# Artemis_Thing_Plus.net
KiCad netlist of a schematic drawn in EAGLE
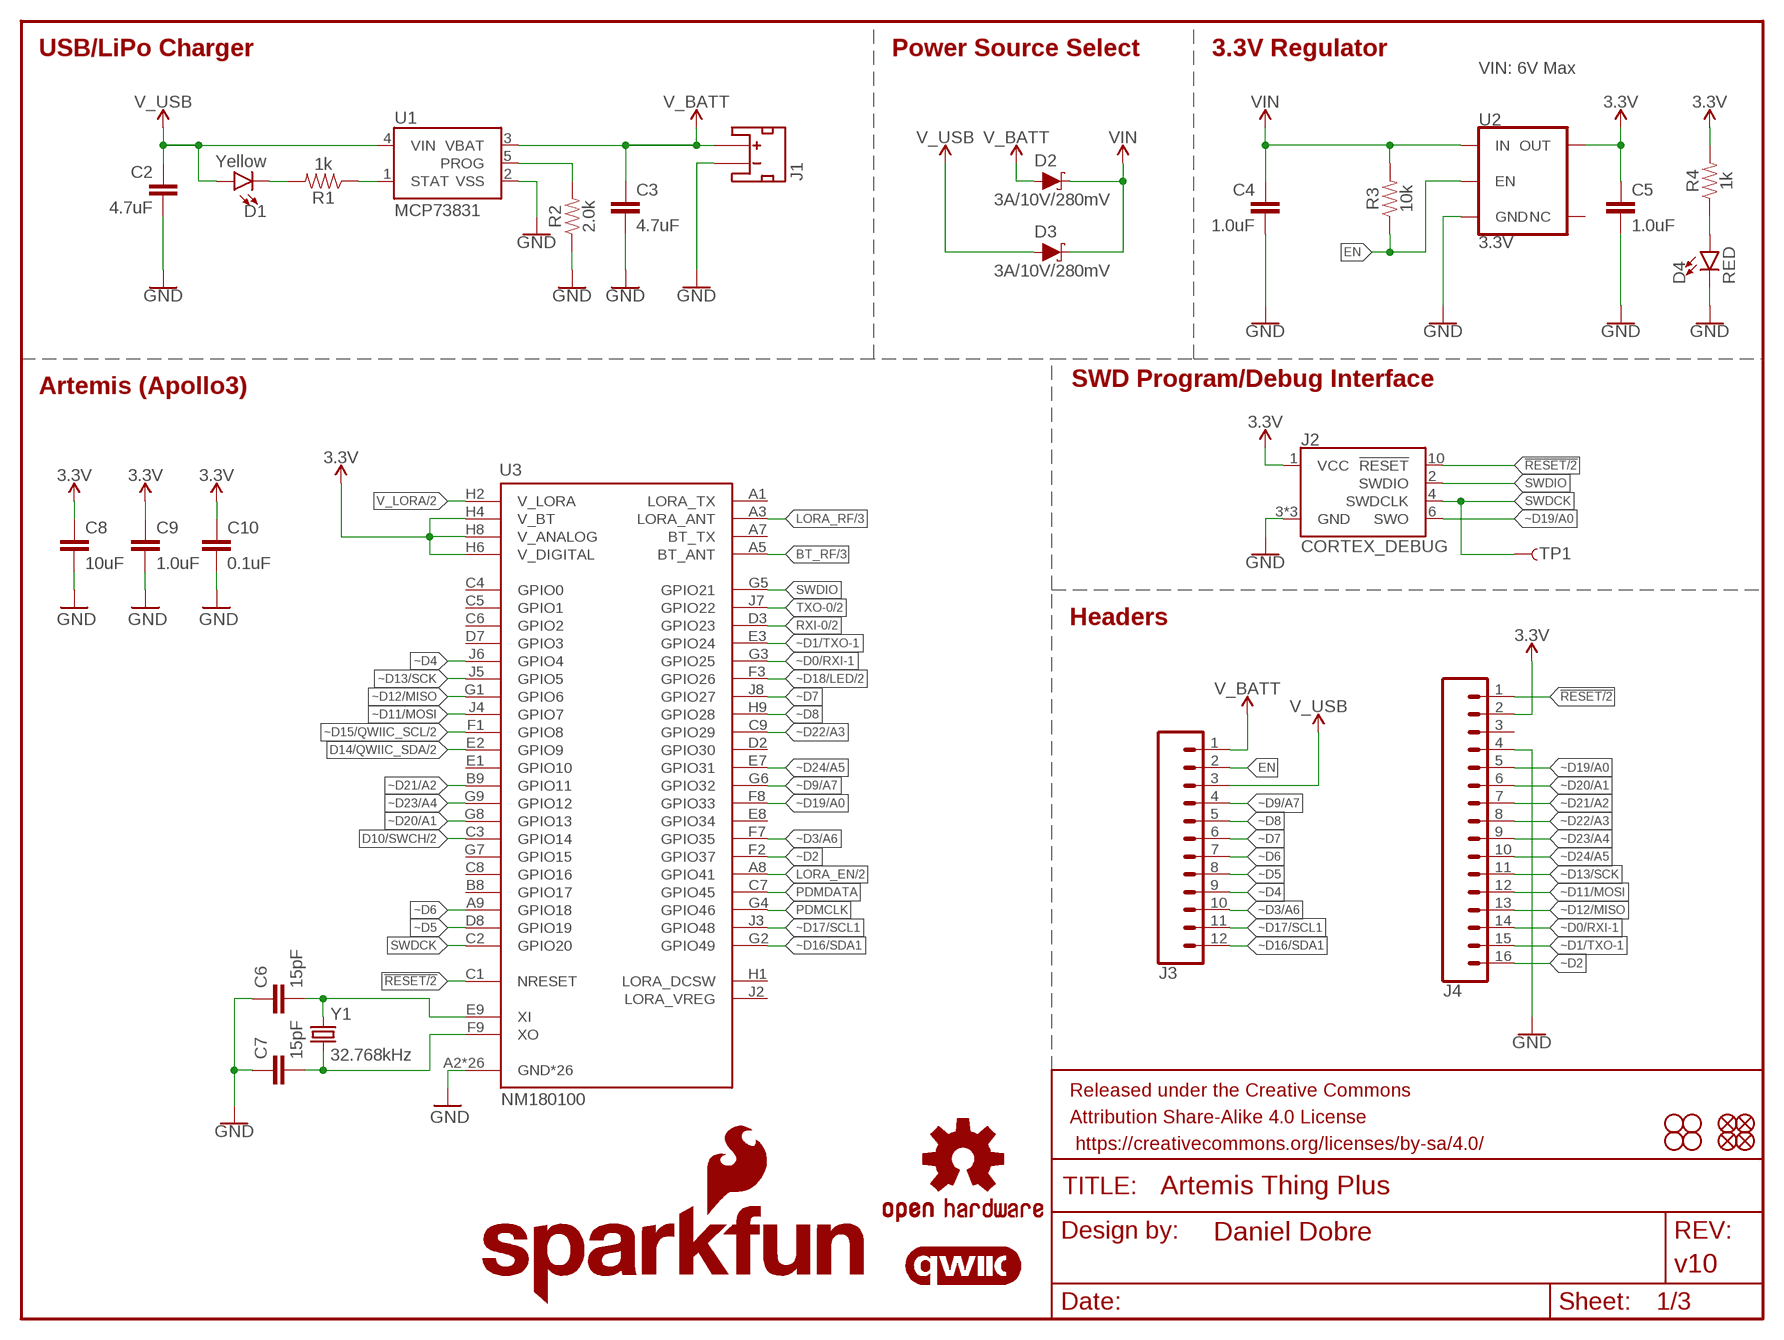
[diagram p0: schematic, sheet 1]
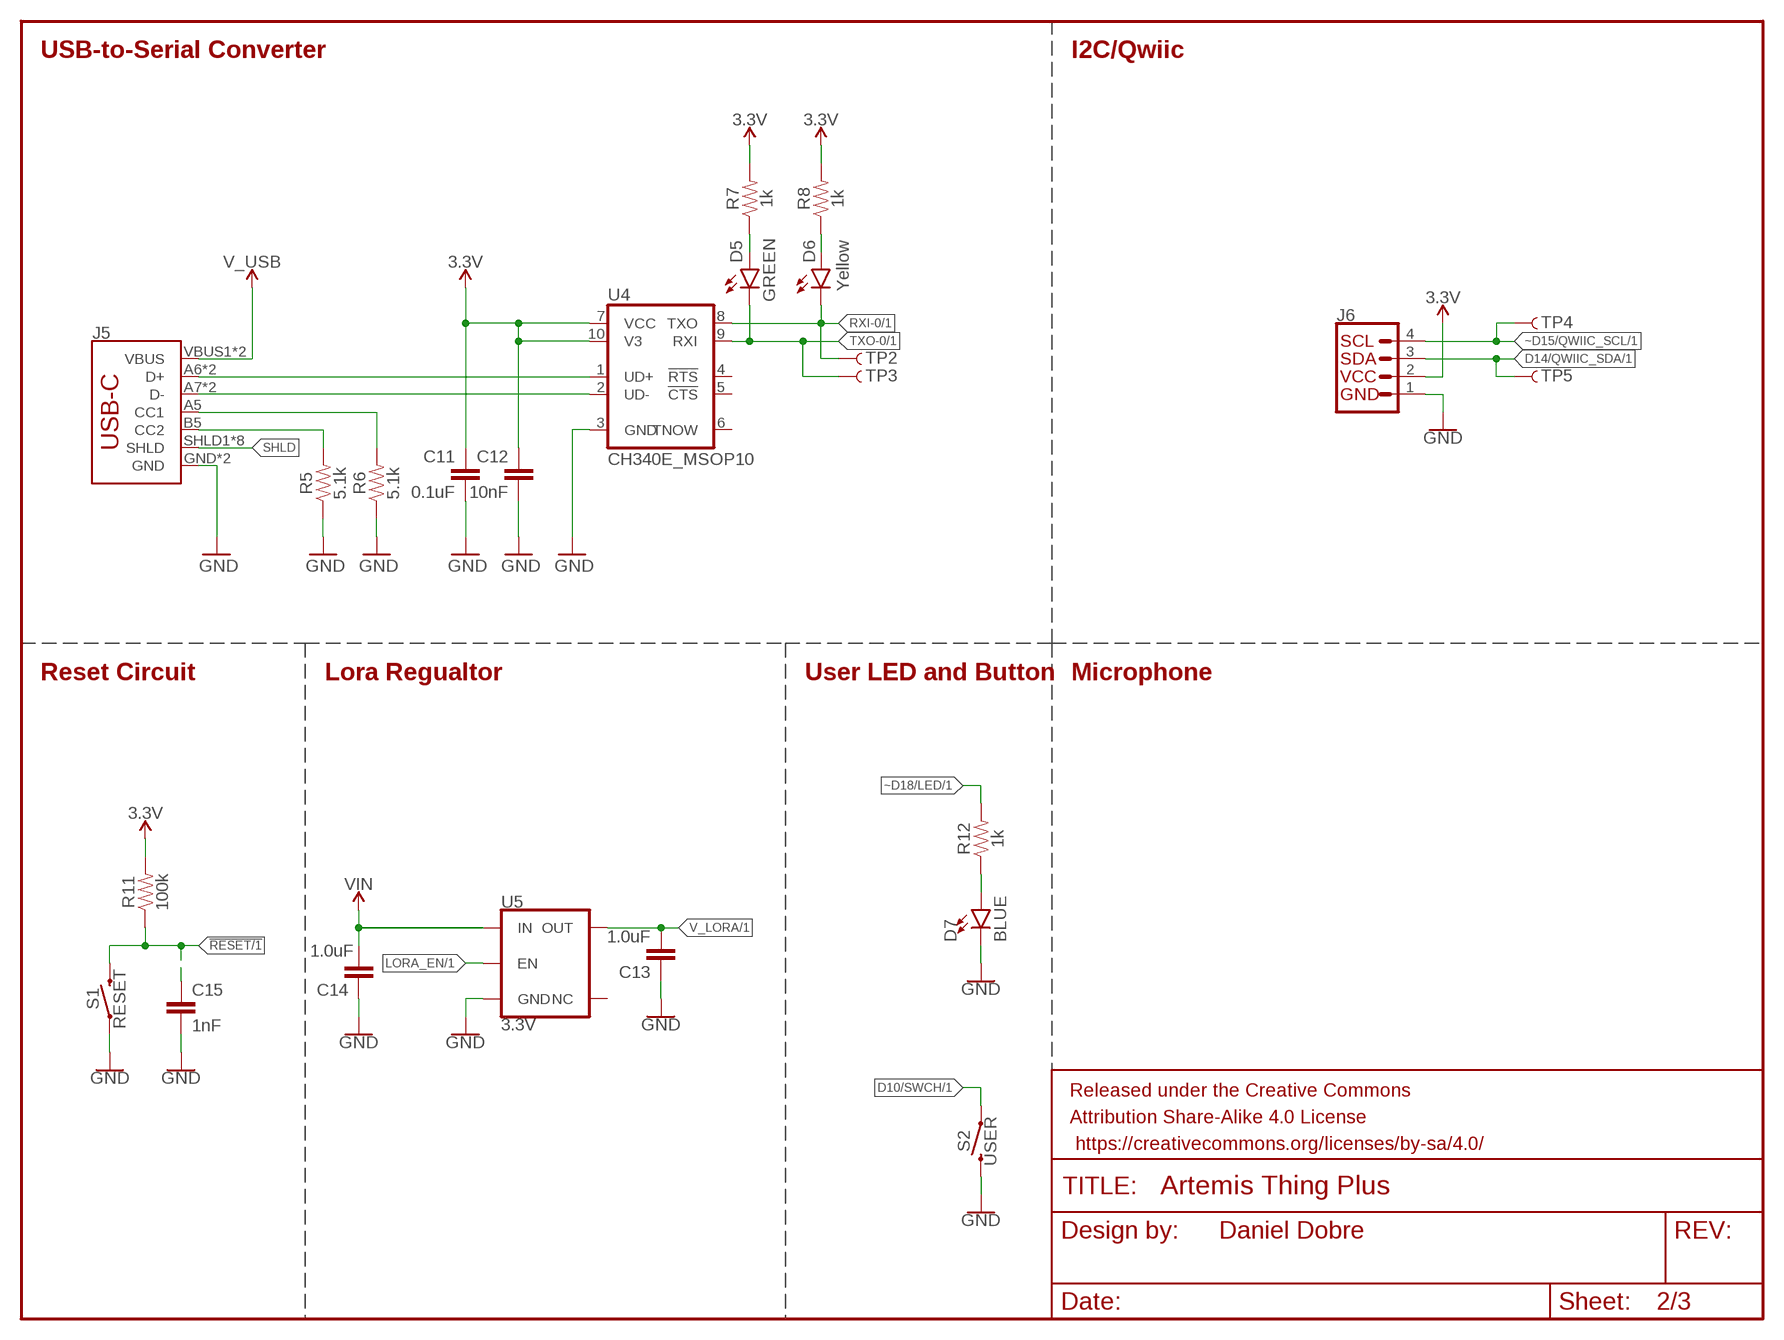
[diagram p1: schematic, sheet 2]
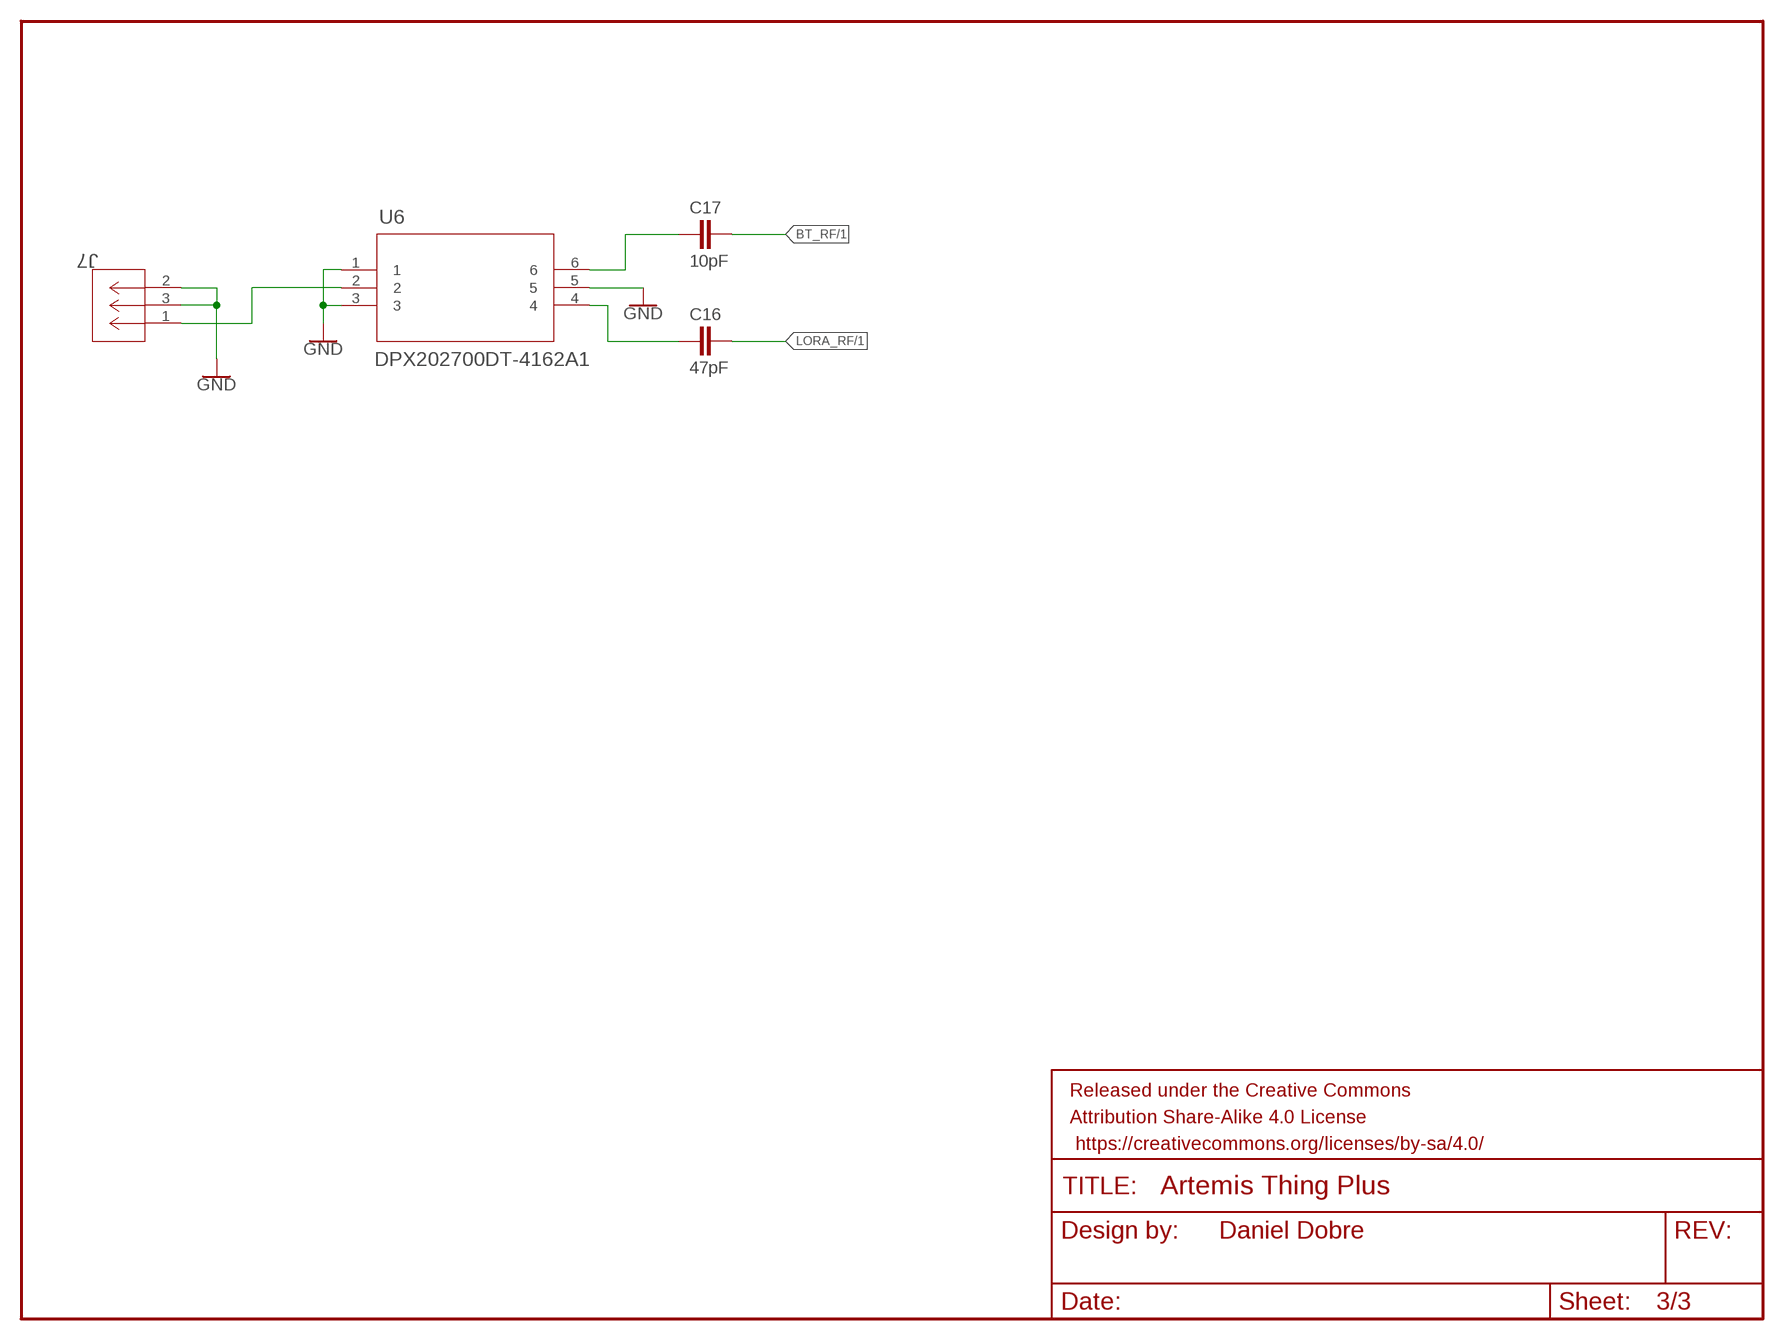
[diagram p2: schematic, sheet 3]

(export (version "E")
  (design (tool "Eeschema 10.0.6"))
  (components
    (comp (ref "C2")
      (value "4.7uF")
      (footprint "eagle-import:0603")
      (libsource (lib "eagle-import") (part "4.7UF-0603-6.3V-(10%)"))
    )
    (comp (ref "C3")
      (value "4.7uF")
      (footprint "eagle-import:0603")
      (libsource (lib "eagle-import") (part "4.7UF-0603-6.3V-(10%)"))
    )
    (comp (ref "C4")
      (value "1.0uF")
      (footprint "eagle-import:0402-TIGHT")
      (libsource (lib "eagle-import") (part "1.0UF-0402T-16V-10%"))
    )
    (comp (ref "C5")
      (value "1.0uF")
      (footprint "eagle-import:0402-TIGHT")
      (libsource (lib "eagle-import") (part "1.0UF-0402T-16V-10%"))
    )
    (comp (ref "C6")
      (value "15pF")
      (footprint "eagle-import:0603")
      (libsource (lib "eagle-import") (part "15PF-0603-50V-5%"))
    )
    (comp (ref "C7")
      (value "15pF")
      (footprint "eagle-import:0603")
      (libsource (lib "eagle-import") (part "15PF-0603-50V-5%"))
    )
    (comp (ref "C8")
      (value "10uF")
      (footprint "eagle-import:0603")
      (libsource (lib "eagle-import") (part "10UF-0603-6.3V-20%"))
    )
    (comp (ref "C9")
      (value "1.0uF")
      (footprint "eagle-import:0603")
      (libsource (lib "eagle-import") (part "1.0UF-0603-16V-10%"))
    )
    (comp (ref "C10")
      (value "0.1uF")
      (footprint "eagle-import:0603")
      (libsource (lib "eagle-import") (part "0.1UF-0603-25V-(+80/-20%)"))
    )
    (comp (ref "D1")
      (value "Yellow")
      (footprint "eagle-import:LED-0603")
      (libsource (lib "eagle-import") (part "LED-YELLOW0603"))
    )
    (comp (ref "D2")
      (value "3A/10V/280mV")
      (footprint "eagle-import:SOD-323")
      (libsource (lib "eagle-import") (part "DIODE-SCHOTTKY-BAT60A"))
    )
    (comp (ref "D3")
      (value "3A/10V/280mV")
      (footprint "eagle-import:SOD-323")
      (libsource (lib "eagle-import") (part "DIODE-SCHOTTKY-BAT60A"))
    )
    (comp (ref "D4")
      (value "RED")
      (footprint "eagle-import:LED-0603")
      (libsource (lib "eagle-import") (part "LED-RED0603"))
    )
    (comp (ref "FD1")
      (value "FIDUCIALUFIDUCIAL")
      (footprint "eagle-import:FIDUCIAL-MICRO")
      (libsource (lib "eagle-import") (part "FIDUCIALUFIDUCIAL"))
    )
    (comp (ref "FD2")
      (value "FIDUCIALUFIDUCIAL")
      (footprint "eagle-import:FIDUCIAL-MICRO")
      (libsource (lib "eagle-import") (part "FIDUCIALUFIDUCIAL"))
    )
    (comp (ref "FD3")
      (value "FIDUCIALUFIDUCIAL")
      (footprint "eagle-import:FIDUCIAL-MICRO")
      (libsource (lib "eagle-import") (part "FIDUCIALUFIDUCIAL"))
    )
    (comp (ref "FD4")
      (value "FIDUCIALUFIDUCIAL")
      (footprint "eagle-import:FIDUCIAL-MICRO")
      (libsource (lib "eagle-import") (part "FIDUCIALUFIDUCIAL"))
    )
    (comp (ref "FRAME1")
      (value "FRAME-LETTER")
      (footprint "eagle-import:CREATIVE_COMMONS")
      (fields (field (name "DESIGNER") "Daniel Dobre") (field (name "REV") "v10"))
      (libsource (lib "eagle-import") (part "FRAME-LETTER"))
    )
    (comp (ref "H1")
      (value "STAND-OFF")
      (footprint "eagle-import:STAND-OFF")
      (libsource (lib "eagle-import") (part "STAND-OFF"))
    )
    (comp (ref "H2")
      (value "STAND-OFF")
      (footprint "eagle-import:STAND-OFF")
      (libsource (lib "eagle-import") (part "STAND-OFF"))
    )
    (comp (ref "H3")
      (value "STAND-OFF")
      (footprint "eagle-import:STAND-OFF")
      (libsource (lib "eagle-import") (part "STAND-OFF"))
    )
    (comp (ref "H4")
      (value "STAND-OFF")
      (footprint "eagle-import:STAND-OFF")
      (libsource (lib "eagle-import") (part "STAND-OFF"))
    )
    (comp (ref "J1")
      (value "JST_2MM_MALE")
      (footprint "eagle-import:JST-2-SMD")
      (libsource (lib "eagle-import") (part "JST_2MM_MALE"))
    )
    (comp (ref "J2")
      (value "CORTEX_DEBUG")
      (footprint "eagle-import:2X5-PTH-1.27MM-NO_SILK")
      (libsource (lib "eagle-import") (part "CORTEX_DEBUG_MINIMUM_PTH_NS"))
    )
    (comp (ref "J3")
      (value "CONN_12SM_SQ_NO_SILK")
      (footprint "eagle-import:1X12_SM_SQ_NOSILK")
      (libsource (lib "eagle-import") (part "CONN_12SM_SQ_NO_SILK"))
    )
    (comp (ref "J4")
      (value "CONN_161X16_SM_SQ_NOSILK")
      (footprint "eagle-import:1X16_SM_SQ_NOSILK")
      (libsource (lib "eagle-import") (part "CONN_161X16_SM_SQ_NOSILK"))
    )
    (comp (ref "LOGO1")
      (value "OSHW-LOGOS")
      (footprint "eagle-import:OSHW-LOGO-S")
      (libsource (lib "eagle-import") (part "OSHW-LOGOS"))
    )
    (comp (ref "LOGO2")
      (value "QWIIC_LOGO_5MM")
      (footprint "eagle-import:QWIIC_5MM")
      (libsource (lib "eagle-import") (part "QWIIC_LOGO_5MM"))
    )
    (comp (ref "LOGO3")
      (value "SFE_LOGO_NAME_FLAME.1_INCH")
      (footprint "eagle-import:SFE_LOGO_NAME_FLAME_.1")
      (libsource (lib "eagle-import") (part "SFE_LOGO_NAME_FLAME.1_INCH"))
    )
    (comp (ref "R1")
      (value "1k")
      (footprint "eagle-import:0603")
      (libsource (lib "eagle-import") (part "1KOHM-0603-1/10W-1%"))
    )
    (comp (ref "R2")
      (value "2.0k")
      (footprint "eagle-import:0603")
      (libsource (lib "eagle-import") (part "2.0KOHM-0603-1/10W-5%"))
    )
    (comp (ref "R3")
      (value "10k")
      (footprint "eagle-import:0603")
      (libsource (lib "eagle-import") (part "10KOHM-0603-1/10W-1%"))
    )
    (comp (ref "R4")
      (value "1k")
      (footprint "eagle-import:0603")
      (libsource (lib "eagle-import") (part "1KOHM-0603-1/10W-1%"))
    )
    (comp (ref "TP1")
      (value "TEST-POINTTP_15TH_THRU")
      (footprint "eagle-import:TP_15TH")
      (libsource (lib "eagle-import") (part "TEST-POINTTP_15TH_THRU"))
    )
    (comp (ref "U1")
      (value "MCP73831")
      (footprint "eagle-import:SOT23-5")
      (libsource (lib "eagle-import") (part "MCP73831"))
    )
    (comp (ref "U2")
      (value "3.3V")
      (footprint "eagle-import:SOT23-5")
      (libsource (lib "eagle-import") (part "V_REG_AP2112K-3.3V"))
    )
    (comp (ref "U3")
      (value "NM180100")
      (footprint "eagle-import:LGA81")
      (libsource (lib "eagle-import") (part "NM180100"))
    )
    (comp (ref "Y1")
      (value "32.768kHz")
      (footprint "eagle-import:CRYSTAL-SMD-3.2X1.5MM")
      (libsource (lib "eagle-import") (part "CRYSTAL-32.768KHZSMD-3.2X1.5"))
    )
    (comp (ref "C11")
      (value "0.1uF")
      (footprint "eagle-import:0603")
      (libsource (lib "eagle-import") (part "0.1UF-0603-25V-(+80/-20%)"))
    )
    (comp (ref "C12")
      (value "10nF")
      (footprint "eagle-import:0603")
      (libsource (lib "eagle-import") (part "10NF-0603-50V-10%"))
    )
    (comp (ref "C13")
      (value "1.0uF")
      (footprint "eagle-import:0603")
      (libsource (lib "eagle-import") (part "SparkFun-Capacitors_510_1.0UF-0603-16V-10%"))
    )
    (comp (ref "C14")
      (value "1.0uF")
      (footprint "eagle-import:0603")
      (libsource (lib "eagle-import") (part "SparkFun-Capacitors_510_1.0UF-0603-16V-10%"))
    )
    (comp (ref "C15")
      (value "1nF")
      (footprint "eagle-import:0603")
      (libsource (lib "eagle-import") (part "1.0NF/1000PF-0603-50V-10%"))
    )
    (comp (ref "D5")
      (value "GREEN")
      (footprint "eagle-import:LED-0603")
      (libsource (lib "eagle-import") (part "LED-GREEN0603"))
    )
    (comp (ref "D6")
      (value "Yellow")
      (footprint "eagle-import:LED-0603")
      (libsource (lib "eagle-import") (part "LED-YELLOW0603"))
    )
    (comp (ref "D7")
      (value "BLUE")
      (footprint "eagle-import:LED-0603")
      (libsource (lib "eagle-import") (part "LED-BLUE0603"))
    )
    (comp (ref "FRAME2")
      (value "FRAME-LETTERNO_PACKAGE")
      (footprint "eagle-import:DUMMY")
      (fields (field (name "DESIGNER") "Nobody"))
      (libsource (lib "eagle-import") (part "FRAME-LETTERNO_PACKAGE"))
    )
    (comp (ref "J5")
      (value "USB-C")
      (footprint "eagle-import:USB-C-16P")
      (libsource (lib "eagle-import") (part "USB_C2-LAYER"))
    )
    (comp (ref "J6")
      (value "QWIIC_CONNECTORJS-1MM")
      (footprint "eagle-import:JST04_1MM_RA")
      (libsource (lib "eagle-import") (part "QWIIC_CONNECTORJS-1MM"))
    )
    (comp (ref "R5")
      (value "5.1k")
      (footprint "eagle-import:0603")
      (libsource (lib "eagle-import") (part "5.1KOHM5.1KOHM-0603-1/10W-1%"))
    )
    (comp (ref "R6")
      (value "5.1k")
      (footprint "eagle-import:0603")
      (libsource (lib "eagle-import") (part "5.1KOHM5.1KOHM-0603-1/10W-1%"))
    )
    (comp (ref "R7")
      (value "1k")
      (footprint "eagle-import:0603")
      (libsource (lib "eagle-import") (part "1KOHM-0603-1/10W-1%"))
    )
    (comp (ref "R8")
      (value "1k")
      (footprint "eagle-import:0603")
      (libsource (lib "eagle-import") (part "1KOHM-0603-1/10W-1%"))
    )
    (comp (ref "R11")
      (value "100k")
      (footprint "eagle-import:0603")
      (libsource (lib "eagle-import") (part "100KOHM-0603-1/10W-1%"))
    )
    (comp (ref "R12")
      (value "1k")
      (footprint "eagle-import:0603")
      (libsource (lib "eagle-import") (part "1KOHM-0603-1/10W-1%"))
    )
    (comp (ref "S1")
      (value "RESET")
      (footprint "eagle-import:TACTILE_SWITCH_SMD_4.6X2.8MM")
      (libsource (lib "eagle-import") (part "MOMENTARY-SWITCH-SPST-SMD-4.6X2.8MM"))
    )
    (comp (ref "S2")
      (value "USER")
      (footprint "eagle-import:TACTILE_SWITCH_SMD_4.6X2.8MM")
      (libsource (lib "eagle-import") (part "MOMENTARY-SWITCH-SPST-SMD-4.6X2.8MM"))
    )
    (comp (ref "TP2")
      (value "TEST-POINTTP_15TH_THRU")
      (footprint "eagle-import:TP_15TH")
      (libsource (lib "eagle-import") (part "TEST-POINTTP_15TH_THRU"))
    )
    (comp (ref "TP3")
      (value "TEST-POINTTP_15TH_THRU")
      (footprint "eagle-import:TP_15TH")
      (libsource (lib "eagle-import") (part "TEST-POINTTP_15TH_THRU"))
    )
    (comp (ref "TP4")
      (value "TEST-POINTTP_15TH_THRU")
      (footprint "eagle-import:TP_15TH")
      (libsource (lib "eagle-import") (part "TEST-POINTTP_15TH_THRU"))
    )
    (comp (ref "TP5")
      (value "TEST-POINTTP_15TH_THRU")
      (footprint "eagle-import:TP_15TH")
      (libsource (lib "eagle-import") (part "TEST-POINTTP_15TH_THRU"))
    )
    (comp (ref "U4")
      (value "CH340E_MSOP10")
      (footprint "eagle-import:MSOP10")
      (libsource (lib "eagle-import") (part "CH340E_MSOP10"))
    )
    (comp (ref "U5")
      (value "3.3V")
      (footprint "eagle-import:SOT23-5")
      (libsource (lib "eagle-import") (part "SparkFun-IC-Power_526_V_REG_AP2112K-3.3V"))
    )
    (comp (ref "C16")
      (value "47pF")
      (footprint "eagle-import:0603")
      (libsource (lib "eagle-import") (part "47PF-0603-50V-5%"))
    )
    (comp (ref "C17")
      (value "10pF")
      (footprint "eagle-import:0603")
      (libsource (lib "eagle-import") (part "10PF-0603-50V-5%"))
    )
    (comp (ref "FRAME3")
      (value "FRAME-LETTERNO_PACKAGE")
      (footprint "eagle-import:DUMMY")
      (fields (field (name "DESIGNER") "Daniel Dobre"))
      (libsource (lib "eagle-import") (part "FRAME-LETTERNO_PACKAGE"))
    )
    (comp (ref "J7")
      (value "U.FL-R-SMT-1(10)")
      (footprint "eagle-import:CONN_R-SMT-1(10)")
      (fields (field (name "COPYRIGHT") "Copyright (C) 2018 Accelerated Designs. All rights reserved"))
      (libsource (lib "eagle-import") (part "U.FL-R-SMT-1(10)"))
    )
    (comp (ref "U6")
      (value "DPX202700DT-4162A1")
      (footprint "eagle-import:RF_4060A1_TDK")
      (fields (field (name "COPYRIGHT") "Copyright (C) 2018 Accelerated Designs. All rights reserved"))
      (libsource (lib "eagle-import") (part "DPX202700DT-4162A1"))
    )
  )
  (nets
    (net (code "1") (name "3.3V") (class "Default")
      (node (ref "C10") (pin "1") (pinfunction "1_1") (pintype "passive"))
      (node (ref "C11") (pin "1") (pinfunction "1_1") (pintype "passive"))
      (node (ref "C12") (pin "1") (pinfunction "1_1") (pintype "passive"))
      (node (ref "C5") (pin "1") (pinfunction "1_1") (pintype "passive"))
      (node (ref "C8") (pin "1") (pinfunction "1_1") (pintype "passive"))
      (node (ref "C9") (pin "1") (pinfunction "1_1") (pintype "passive"))
      (node (ref "J2") (pin "1") (pinfunction "VCC_1") (pintype "bidirectional"))
      (node (ref "J4") (pin "2") (pinfunction "2_2") (pintype "passive"))
      (node (ref "J6") (pin "2") (pinfunction "2_2") (pintype "power_in"))
      (node (ref "R11") (pin "2") (pinfunction "2_2") (pintype "passive"))
      (node (ref "R4") (pin "2") (pinfunction "2_2") (pintype "passive"))
      (node (ref "R7") (pin "2") (pinfunction "2_2") (pintype "passive"))
      (node (ref "R8") (pin "2") (pinfunction "2_2") (pintype "passive"))
      (node (ref "U2") (pin "5") (pinfunction "OUT_5") (pintype "passive"))
      (node (ref "U3") (pin "H4") (pinfunction "V_BT_H4") (pintype "bidirectional"))
      (node (ref "U3") (pin "H6") (pinfunction "V_DIGITAL_H6") (pintype "bidirectional"))
      (node (ref "U3") (pin "H8") (pinfunction "V_ANALOG_H8") (pintype "bidirectional"))
      (node (ref "U4") (pin "10") (pinfunction "V3_10") (pintype "bidirectional"))
      (node (ref "U4") (pin "7") (pinfunction "VCC_7") (pintype "bidirectional"))
    )
    (net (code "2") (name "BT_RF") (class "Default")
      (node (ref "C17") (pin "1") (pinfunction "1_1") (pintype "passive"))
      (node (ref "U3") (pin "A5") (pinfunction "BT_ANT_A5") (pintype "bidirectional"))
    )
    (net (code "3") (name "D10{slash}SWCH") (class "Default")
      (node (ref "S2") (pin "1") (pinfunction "1_1") (pintype "passive"))
      (node (ref "S2") (pin "2") (pinfunction "1_2") (pintype "passive"))
      (node (ref "U3") (pin "C3") (pinfunction "GPIO14_C3") (pintype "bidirectional"))
    )
    (net (code "4") (name "D14{slash}QWIIC_SDA") (class "Default")
      (node (ref "J6") (pin "3") (pinfunction "3_3") (pintype "passive"))
      (node (ref "TP5") (pin "P$1") (pinfunction "1_P$1") (pintype "bidirectional"))
      (node (ref "U3") (pin "E2") (pinfunction "GPIO9_E2") (pintype "bidirectional"))
    )
    (net (code "5") (name "EN") (class "Default")
      (node (ref "J3") (pin "2") (pinfunction "2_2") (pintype "passive"))
      (node (ref "R3") (pin "1") (pinfunction "1_1") (pintype "passive"))
      (node (ref "U2") (pin "3") (pinfunction "EN_3") (pintype "input"))
    )
    (net (code "6") (name "GND") (class "Default")
      (node (ref "C10") (pin "2") (pinfunction "2_2") (pintype "passive"))
      (node (ref "C11") (pin "2") (pinfunction "2_2") (pintype "passive"))
      (node (ref "C12") (pin "2") (pinfunction "2_2") (pintype "passive"))
      (node (ref "C13") (pin "1") (pinfunction "1_1") (pintype "passive"))
      (node (ref "C14") (pin "1") (pinfunction "1_1") (pintype "passive"))
      (node (ref "C15") (pin "2") (pinfunction "2_2") (pintype "passive"))
      (node (ref "C2") (pin "2") (pinfunction "2_2") (pintype "passive"))
      (node (ref "C3") (pin "2") (pinfunction "2_2") (pintype "passive"))
      (node (ref "C4") (pin "2") (pinfunction "2_2") (pintype "passive"))
      (node (ref "C5") (pin "2") (pinfunction "2_2") (pintype "passive"))
      (node (ref "C6") (pin "1") (pinfunction "1_1") (pintype "passive"))
      (node (ref "C7") (pin "1") (pinfunction "1_1") (pintype "passive"))
      (node (ref "C8") (pin "2") (pinfunction "2_2") (pintype "passive"))
      (node (ref "C9") (pin "2") (pinfunction "2_2") (pintype "passive"))
      (node (ref "D4") (pin "C") (pinfunction "C_C") (pintype "passive"))
      (node (ref "D7") (pin "C") (pinfunction "C_C") (pintype "passive"))
      (node (ref "J1") (pin "1") (pinfunction "-_1") (pintype "bidirectional"))
      (node (ref "J2") (pin "3") (pinfunction "GND_3") (pintype "bidirectional"))
      (node (ref "J2") (pin "5") (pinfunction "GND_5") (pintype "bidirectional"))
      (node (ref "J2") (pin "9") (pinfunction "GND_9") (pintype "bidirectional"))
      (node (ref "J4") (pin "4") (pinfunction "4_4") (pintype "passive"))
      (node (ref "J5") (pin "GND") (pinfunction "GND_GND") (pintype "bidirectional"))
      (node (ref "J5") (pin "GND2") (pinfunction "GND_GND2") (pintype "bidirectional"))
      (node (ref "J6") (pin "1") (pinfunction "1_1") (pintype "power_in"))
      (node (ref "J7") (pin "2") (pinfunction "2_2") (pintype "passive"))
      (node (ref "J7") (pin "3") (pinfunction "3_3") (pintype "passive"))
      (node (ref "R2") (pin "1") (pinfunction "1_1") (pintype "passive"))
      (node (ref "R5") (pin "1") (pinfunction "1_1") (pintype "passive"))
      (node (ref "R6") (pin "1") (pinfunction "1_1") (pintype "passive"))
      (node (ref "S1") (pin "1") (pinfunction "1_1") (pintype "passive"))
      (node (ref "S1") (pin "2") (pinfunction "1_2") (pintype "passive"))
      (node (ref "S2") (pin "3") (pinfunction "2_3") (pintype "passive"))
      (node (ref "S2") (pin "4") (pinfunction "2_4") (pintype "passive"))
      (node (ref "U1") (pin "2") (pinfunction "VSS_2") (pintype "power_in"))
      (node (ref "U2") (pin "2") (pinfunction "GND_2") (pintype "input"))
      (node (ref "U3") (pin "A2") (pinfunction "GND*26_A2") (pintype "bidirectional"))
      (node (ref "U3") (pin "A4") (pinfunction "GND*26_A4") (pintype "bidirectional"))
      (node (ref "U3") (pin "A6") (pinfunction "GND*26_A6") (pintype "bidirectional"))
      (node (ref "U3") (pin "B1") (pinfunction "GND*26_B1") (pintype "bidirectional"))
      (node (ref "U3") (pin "B2") (pinfunction "GND*26_B2") (pintype "bidirectional"))
      (node (ref "U3") (pin "B3") (pinfunction "GND*26_B3") (pintype "bidirectional"))
      (node (ref "U3") (pin "B4") (pinfunction "GND*26_B4") (pintype "bidirectional"))
      (node (ref "U3") (pin "B5") (pinfunction "GND*26_B5") (pintype "bidirectional"))
      (node (ref "U3") (pin "B6") (pinfunction "GND*26_B6") (pintype "bidirectional"))
      (node (ref "U3") (pin "B7") (pinfunction "GND*26_B7") (pintype "bidirectional"))
      (node (ref "U3") (pin "D1") (pinfunction "GND*26_D1") (pintype "bidirectional"))
      (node (ref "U3") (pin "D4") (pinfunction "GND*26_D4") (pintype "bidirectional"))
      (node (ref "U3") (pin "D5") (pinfunction "GND*26_D5") (pintype "bidirectional"))
      (node (ref "U3") (pin "D6") (pinfunction "GND*26_D6") (pintype "bidirectional"))
      (node (ref "U3") (pin "D9") (pinfunction "GND*26_D9") (pintype "bidirectional"))
      (node (ref "U3") (pin "E4") (pinfunction "GND*26_E4") (pintype "bidirectional"))
      (node (ref "U3") (pin "E5") (pinfunction "GND*26_E5") (pintype "bidirectional"))
      (node (ref "U3") (pin "E6") (pinfunction "GND*26_E6") (pintype "bidirectional"))
      (node (ref "U3") (pin "F4") (pinfunction "GND*26_F4") (pintype "bidirectional"))
      (node (ref "U3") (pin "F5") (pinfunction "GND*26_F5") (pintype "bidirectional"))
      (node (ref "U3") (pin "F6") (pinfunction "GND*26_F6") (pintype "bidirectional"))
      (node (ref "U3") (pin "H3") (pinfunction "GND*26_H3") (pintype "bidirectional"))
      (node (ref "U3") (pin "H5") (pinfunction "GND*26_H5") (pintype "bidirectional"))
      (node (ref "U3") (pin "H7") (pinfunction "GND*26_H7") (pintype "bidirectional"))
      (node (ref "U3") (pin "J1") (pinfunction "GND*26_J1") (pintype "bidirectional"))
      (node (ref "U3") (pin "J9") (pinfunction "GND*26_J9") (pintype "bidirectional"))
      (node (ref "U4") (pin "3") (pinfunction "GND_3") (pintype "bidirectional"))
      (node (ref "U5") (pin "2") (pinfunction "GND_2") (pintype "input"))
      (node (ref "U6") (pin "1") (pinfunction "1_1") (pintype "passive"))
      (node (ref "U6") (pin "3") (pinfunction "3_3") (pintype "passive"))
      (node (ref "U6") (pin "5") (pinfunction "5_5") (pintype "passive"))
    )
    (net (code "7") (name "LORA_EN") (class "Default")
      (node (ref "U3") (pin "A8") (pinfunction "GPIO41_A8") (pintype "bidirectional"))
      (node (ref "U5") (pin "3") (pinfunction "EN_3") (pintype "input"))
    )
    (net (code "8") (name "LORA_RF") (class "Default")
      (node (ref "C16") (pin "1") (pinfunction "1_1") (pintype "passive"))
      (node (ref "U3") (pin "A3") (pinfunction "LORA_ANT_A3") (pintype "bidirectional"))
    )
    (net (code "9") (name "Net-(C16-Pad2)") (class "Default")
      (node (ref "C16") (pin "2") (pinfunction "2_2") (pintype "passive"))
      (node (ref "U6") (pin "4") (pinfunction "4_4") (pintype "passive"))
    )
    (net (code "10") (name "Net-(C17-Pad2)") (class "Default")
      (node (ref "C17") (pin "2") (pinfunction "2_2") (pintype "passive"))
      (node (ref "U6") (pin "6") (pinfunction "6_6") (pintype "passive"))
    )
    (net (code "11") (name "Net-(D1-PadC)") (class "Default")
      (node (ref "D1") (pin "C") (pinfunction "C_C") (pintype "passive"))
      (node (ref "R1") (pin "2") (pinfunction "2_2") (pintype "passive"))
    )
    (net (code "12") (name "Net-(D4-PadA)") (class "Default")
      (node (ref "D4") (pin "A") (pinfunction "A_A") (pintype "passive"))
      (node (ref "R4") (pin "1") (pinfunction "1_1") (pintype "passive"))
    )
    (net (code "13") (name "Net-(D5-PadA)") (class "Default")
      (node (ref "D5") (pin "A") (pinfunction "A_A") (pintype "passive"))
      (node (ref "R7") (pin "1") (pinfunction "1_1") (pintype "passive"))
    )
    (net (code "14") (name "Net-(D6-PadA)") (class "Default")
      (node (ref "D6") (pin "A") (pinfunction "A_A") (pintype "passive"))
      (node (ref "R8") (pin "1") (pinfunction "1_1") (pintype "passive"))
    )
    (net (code "15") (name "Net-(D7-PadA)") (class "Default")
      (node (ref "D7") (pin "A") (pinfunction "A_A") (pintype "passive"))
      (node (ref "R12") (pin "1") (pinfunction "1_1") (pintype "passive"))
    )
    (net (code "16") (name "Net-(J5-CC1)") (class "Default")
      (node (ref "J5") (pin "A5") (pinfunction "CC1_A5") (pintype "bidirectional"))
      (node (ref "R6") (pin "2") (pinfunction "2_2") (pintype "passive"))
    )
    (net (code "17") (name "Net-(J5-CC2)") (class "Default")
      (node (ref "J5") (pin "B5") (pinfunction "CC2_B5") (pintype "bidirectional"))
      (node (ref "R5") (pin "2") (pinfunction "2_2") (pintype "passive"))
    )
    (net (code "18") (name "Net-(J7-Pad1)") (class "Default")
      (node (ref "J7") (pin "1") (pinfunction "1_1") (pintype "passive"))
      (node (ref "U6") (pin "2") (pinfunction "2_2") (pintype "passive"))
    )
    (net (code "19") (name "Net-(U1-PROG)") (class "Default")
      (node (ref "R2") (pin "2") (pinfunction "2_2") (pintype "passive"))
      (node (ref "U1") (pin "5") (pinfunction "PROG_5") (pintype "input"))
    )
    (net (code "20") (name "Net-(U1-STAT)") (class "Default")
      (node (ref "R1") (pin "1") (pinfunction "1_1") (pintype "passive"))
      (node (ref "U1") (pin "1") (pinfunction "STAT_1") (pintype "output"))
    )
    (net (code "21") (name "Net-(U3-XI)") (class "Default")
      (node (ref "C6") (pin "2") (pinfunction "2_2") (pintype "passive"))
      (node (ref "U3") (pin "E9") (pinfunction "XI_E9") (pintype "bidirectional"))
      (node (ref "Y1") (pin "P$1") (pinfunction "1_P$1") (pintype "passive"))
    )
    (net (code "22") (name "Net-(U3-XO)") (class "Default")
      (node (ref "C7") (pin "2") (pinfunction "2_2") (pintype "passive"))
      (node (ref "U3") (pin "F9") (pinfunction "XO_F9") (pintype "bidirectional"))
      (node (ref "Y1") (pin "P$2") (pinfunction "2_P$2") (pintype "passive"))
    )
    (net (code "23") (name "Net-(U4-UD+)") (class "Default")
      (node (ref "J5") (pin "A6") (pinfunction "D+_A6") (pintype "bidirectional"))
      (node (ref "J5") (pin "B6") (pinfunction "D+_B6") (pintype "bidirectional"))
      (node (ref "U4") (pin "1") (pinfunction "UD+_1") (pintype "bidirectional"))
    )
    (net (code "24") (name "Net-(U4-UD-)") (class "Default")
      (node (ref "J5") (pin "A7") (pinfunction "D-_A7") (pintype "bidirectional"))
      (node (ref "J5") (pin "B7") (pinfunction "D-_B7") (pintype "bidirectional"))
      (node (ref "U4") (pin "2") (pinfunction "UD-_2") (pintype "bidirectional"))
    )
    (net (code "25") (name "PDMCLK") (class "Default")
      (node (ref "U3") (pin "G4") (pinfunction "GPIO46_G4") (pintype "bidirectional"))
    )
    (net (code "26") (name "PDMDATA") (class "Default")
      (node (ref "U3") (pin "C7") (pinfunction "GPIO45_C7") (pintype "bidirectional"))
    )
    (net (code "27") (name "RXI-0") (class "Default")
      (node (ref "D6") (pin "C") (pinfunction "C_C") (pintype "passive"))
      (node (ref "TP2") (pin "P$1") (pinfunction "1_P$1") (pintype "bidirectional"))
      (node (ref "U3") (pin "D3") (pinfunction "GPIO23_D3") (pintype "bidirectional"))
      (node (ref "U4") (pin "8") (pinfunction "TXO_8") (pintype "bidirectional"))
    )
    (net (code "28") (name "SHLD") (class "Default")
      (node (ref "J5") (pin "SHLD1") (pinfunction "SHLD_SHLD1") (pintype "bidirectional"))
      (node (ref "J5") (pin "SHLD2") (pinfunction "SHLD_SHLD2") (pintype "bidirectional"))
      (node (ref "J5") (pin "SHLD3") (pinfunction "SHLD_SHLD3") (pintype "bidirectional"))
      (node (ref "J5") (pin "SHLD4") (pinfunction "SHLD_SHLD4") (pintype "bidirectional"))
      (node (ref "J5") (pin "SHLD5") (pinfunction "SHLD_SHLD5") (pintype "bidirectional"))
      (node (ref "J5") (pin "SHLD6") (pinfunction "SHLD_SHLD6") (pintype "bidirectional"))
      (node (ref "J5") (pin "SHLD7") (pinfunction "SHLD_SHLD7") (pintype "bidirectional"))
      (node (ref "J5") (pin "SHLD8") (pinfunction "SHLD_SHLD8") (pintype "bidirectional"))
    )
    (net (code "29") (name "SWDCK") (class "Default")
      (node (ref "J2") (pin "4") (pinfunction "SWDCLK_4") (pintype "bidirectional"))
      (node (ref "TP1") (pin "P$1") (pinfunction "1_P$1") (pintype "bidirectional"))
      (node (ref "U3") (pin "C2") (pinfunction "GPIO20_C2") (pintype "bidirectional"))
    )
    (net (code "30") (name "SWDIO") (class "Default")
      (node (ref "J2") (pin "2") (pinfunction "SWDIO_2") (pintype "bidirectional"))
      (node (ref "U3") (pin "G5") (pinfunction "GPIO21_G5") (pintype "bidirectional"))
    )
    (net (code "31") (name "TXO-0") (class "Default")
      (node (ref "D5") (pin "C") (pinfunction "C_C") (pintype "passive"))
      (node (ref "TP3") (pin "P$1") (pinfunction "1_P$1") (pintype "bidirectional"))
      (node (ref "U3") (pin "J7") (pinfunction "GPIO22_J7") (pintype "bidirectional"))
      (node (ref "U4") (pin "9") (pinfunction "RXI_9") (pintype "bidirectional"))
    )
    (net (code "32") (name "VIN") (class "Default")
      (node (ref "C14") (pin "2") (pinfunction "2_2") (pintype "passive"))
      (node (ref "C4") (pin "1") (pinfunction "1_1") (pintype "passive"))
      (node (ref "D2") (pin "C") (pinfunction "C_C") (pintype "passive"))
      (node (ref "D3") (pin "C") (pinfunction "C_C") (pintype "passive"))
      (node (ref "R3") (pin "2") (pinfunction "2_2") (pintype "passive"))
      (node (ref "U2") (pin "1") (pinfunction "IN_1") (pintype "input"))
      (node (ref "U5") (pin "1") (pinfunction "IN_1") (pintype "input"))
    )
    (net (code "33") (name "V_BATT") (class "Default")
      (node (ref "C3") (pin "1") (pinfunction "1_1") (pintype "passive"))
      (node (ref "D2") (pin "A") (pinfunction "A_A") (pintype "passive"))
      (node (ref "J1") (pin "2") (pinfunction "+_2") (pintype "bidirectional"))
      (node (ref "J3") (pin "1") (pinfunction "1_1") (pintype "passive"))
      (node (ref "U1") (pin "3") (pinfunction "VBAT_3") (pintype "power_in"))
    )
    (net (code "34") (name "V_LORA") (class "Default")
      (node (ref "C13") (pin "2") (pinfunction "2_2") (pintype "passive"))
      (node (ref "U3") (pin "H2") (pinfunction "V_LORA_H2") (pintype "bidirectional"))
      (node (ref "U5") (pin "5") (pinfunction "OUT_5") (pintype "passive"))
    )
    (net (code "35") (name "V_USB") (class "Default")
      (node (ref "C2") (pin "1") (pinfunction "1_1") (pintype "passive"))
      (node (ref "D1") (pin "A") (pinfunction "A_A") (pintype "passive"))
      (node (ref "D3") (pin "A") (pinfunction "A_A") (pintype "passive"))
      (node (ref "J3") (pin "3") (pinfunction "3_3") (pintype "passive"))
      (node (ref "J5") (pin "VBUS1") (pinfunction "VBUS_VBUS1") (pintype "bidirectional"))
      (node (ref "J5") (pin "VBUS2") (pinfunction "VBUS_VBUS2") (pintype "bidirectional"))
      (node (ref "U1") (pin "4") (pinfunction "VIN_4") (pintype "power_in"))
    )
    (net (code "36") (name "unconnected-(J1-PAD1-PadNC1)") (class "Default")
      (node (ref "J1") (pin "NC1") (pinfunction "PAD1_NC1") (pintype "bidirectional"))
    )
    (net (code "37") (name "unconnected-(J1-PAD2-PadNC2)") (class "Default")
      (node (ref "J1") (pin "NC2") (pinfunction "PAD2_NC2") (pintype "bidirectional"))
    )
    (net (code "38") (name "unconnected-(J4-Pad3)") (class "Default")
      (node (ref "J4") (pin "3") (pinfunction "3_3") (pintype "passive"))
    )
    (net (code "39") (name "unconnected-(U2-NC-Pad4)") (class "Default")
      (node (ref "U2") (pin "4") (pinfunction "NC_4") (pintype "no_connect"))
    )
    (net (code "40") (name "unconnected-(U3-BT_TX-PadA7)") (class "Default")
      (node (ref "U3") (pin "A7") (pinfunction "BT_TX_A7") (pintype "bidirectional"))
    )
    (net (code "41") (name "unconnected-(U3-GPIO0-PadC4)") (class "Default")
      (node (ref "U3") (pin "C4") (pinfunction "GPIO0_C4") (pintype "bidirectional"))
    )
    (net (code "42") (name "unconnected-(U3-GPIO1-PadC5)") (class "Default")
      (node (ref "U3") (pin "C5") (pinfunction "GPIO1_C5") (pintype "bidirectional"))
    )
    (net (code "43") (name "unconnected-(U3-GPIO2-PadC6)") (class "Default")
      (node (ref "U3") (pin "C6") (pinfunction "GPIO2_C6") (pintype "bidirectional"))
    )
    (net (code "44") (name "unconnected-(U3-GPIO3-PadD7)") (class "Default")
      (node (ref "U3") (pin "D7") (pinfunction "GPIO3_D7") (pintype "bidirectional"))
    )
    (net (code "45") (name "unconnected-(U3-GPIO10-PadE1)") (class "Default")
      (node (ref "U3") (pin "E1") (pinfunction "GPIO10_E1") (pintype "bidirectional"))
    )
    (net (code "46") (name "unconnected-(U3-GPIO15-PadG7)") (class "Default")
      (node (ref "U3") (pin "G7") (pinfunction "GPIO15_G7") (pintype "bidirectional"))
    )
    (net (code "47") (name "unconnected-(U3-GPIO16-PadC8)") (class "Default")
      (node (ref "U3") (pin "C8") (pinfunction "GPIO16_C8") (pintype "bidirectional"))
    )
    (net (code "48") (name "unconnected-(U3-GPIO17-PadB8)") (class "Default")
      (node (ref "U3") (pin "B8") (pinfunction "GPIO17_B8") (pintype "bidirectional"))
    )
    (net (code "49") (name "unconnected-(U3-GPIO30-PadD2)") (class "Default")
      (node (ref "U3") (pin "D2") (pinfunction "GPIO30_D2") (pintype "bidirectional"))
    )
    (net (code "50") (name "unconnected-(U3-GPIO34-PadE8)") (class "Default")
      (node (ref "U3") (pin "E8") (pinfunction "GPIO34_E8") (pintype "bidirectional"))
    )
    (net (code "51") (name "unconnected-(U3-LORA_DCSW-PadH1)") (class "Default")
      (node (ref "U3") (pin "H1") (pinfunction "LORA_DCSW_H1") (pintype "bidirectional"))
    )
    (net (code "52") (name "unconnected-(U3-LORA_TX-PadA1)") (class "Default")
      (node (ref "U3") (pin "A1") (pinfunction "LORA_TX_A1") (pintype "bidirectional"))
    )
    (net (code "53") (name "unconnected-(U3-LORA_VREG-PadJ2)") (class "Default")
      (node (ref "U3") (pin "J2") (pinfunction "LORA_VREG_J2") (pintype "bidirectional"))
    )
    (net (code "54") (name "unconnected-(U4-TNOW-Pad6)") (class "Default")
      (node (ref "U4") (pin "6") (pinfunction "TNOW_6") (pintype "bidirectional"))
    )
    (net (code "55") (name "unconnected-(U4-~{CTS}-Pad5)") (class "Default")
      (node (ref "U4") (pin "5") (pinfunction "~{CTS}_5") (pintype "bidirectional"))
    )
    (net (code "56") (name "unconnected-(U4-~{RTS}-Pad4)") (class "Default")
      (node (ref "U4") (pin "4") (pinfunction "~{RTS}_4") (pintype "bidirectional"))
    )
    (net (code "57") (name "unconnected-(U5-NC-Pad4)") (class "Default")
      (node (ref "U5") (pin "4") (pinfunction "NC_4") (pintype "no_connect"))
    )
    (net (code "58") (name "~{D0{slash}RXI-1}") (class "Default")
      (node (ref "J4") (pin "14") (pinfunction "14_14") (pintype "passive"))
      (node (ref "U3") (pin "G3") (pinfunction "GPIO25_G3") (pintype "bidirectional"))
    )
    (net (code "59") (name "~{D1{slash}TXO-1}") (class "Default")
      (node (ref "J4") (pin "15") (pinfunction "15_15") (pintype "passive"))
      (node (ref "U3") (pin "E3") (pinfunction "GPIO24_E3") (pintype "bidirectional"))
    )
    (net (code "60") (name "~{D2}") (class "Default")
      (node (ref "J4") (pin "16") (pinfunction "16_16") (pintype "passive"))
      (node (ref "U3") (pin "F2") (pinfunction "GPIO37_F2") (pintype "bidirectional"))
    )
    (net (code "61") (name "~{D3{slash}A6}") (class "Default")
      (node (ref "J3") (pin "10") (pinfunction "10_10") (pintype "passive"))
      (node (ref "U3") (pin "F7") (pinfunction "GPIO35_F7") (pintype "bidirectional"))
    )
    (net (code "62") (name "~{D4}") (class "Default")
      (node (ref "J3") (pin "9") (pinfunction "9_9") (pintype "passive"))
      (node (ref "U3") (pin "J6") (pinfunction "GPIO4_J6") (pintype "bidirectional"))
    )
    (net (code "63") (name "~{D5}") (class "Default")
      (node (ref "J3") (pin "8") (pinfunction "8_8") (pintype "passive"))
      (node (ref "U3") (pin "D8") (pinfunction "GPIO19_D8") (pintype "bidirectional"))
    )
    (net (code "64") (name "~{D6}") (class "Default")
      (node (ref "J3") (pin "7") (pinfunction "7_7") (pintype "passive"))
      (node (ref "U3") (pin "A9") (pinfunction "GPIO18_A9") (pintype "bidirectional"))
    )
    (net (code "65") (name "~{D7}") (class "Default")
      (node (ref "J3") (pin "6") (pinfunction "6_6") (pintype "passive"))
      (node (ref "U3") (pin "J8") (pinfunction "GPIO27_J8") (pintype "bidirectional"))
    )
    (net (code "66") (name "~{D8}") (class "Default")
      (node (ref "J3") (pin "5") (pinfunction "5_5") (pintype "passive"))
      (node (ref "U3") (pin "H9") (pinfunction "GPIO28_H9") (pintype "bidirectional"))
    )
    (net (code "67") (name "~{D9{slash}A7}") (class "Default")
      (node (ref "J3") (pin "4") (pinfunction "4_4") (pintype "passive"))
      (node (ref "U3") (pin "G6") (pinfunction "GPIO32_G6") (pintype "bidirectional"))
    )
    (net (code "68") (name "~{D11{slash}MOSI}") (class "Default")
      (node (ref "J4") (pin "12") (pinfunction "12_12") (pintype "passive"))
      (node (ref "U3") (pin "J4") (pinfunction "GPIO7_J4") (pintype "bidirectional"))
    )
    (net (code "69") (name "~{D12{slash}MISO}") (class "Default")
      (node (ref "J4") (pin "13") (pinfunction "13_13") (pintype "passive"))
      (node (ref "U3") (pin "G1") (pinfunction "GPIO6_G1") (pintype "bidirectional"))
    )
    (net (code "70") (name "~{D13{slash}SCK}") (class "Default")
      (node (ref "J4") (pin "11") (pinfunction "11_11") (pintype "passive"))
      (node (ref "U3") (pin "J5") (pinfunction "GPIO5_J5") (pintype "bidirectional"))
    )
    (net (code "71") (name "~{D15{slash}QWIIC_SCL}") (class "Default")
      (node (ref "J6") (pin "4") (pinfunction "4_4") (pintype "passive"))
      (node (ref "TP4") (pin "P$1") (pinfunction "1_P$1") (pintype "bidirectional"))
      (node (ref "U3") (pin "F1") (pinfunction "GPIO8_F1") (pintype "bidirectional"))
    )
    (net (code "72") (name "~{D16{slash}SDA1}") (class "Default")
      (node (ref "J3") (pin "12") (pinfunction "12_12") (pintype "passive"))
      (node (ref "U3") (pin "G2") (pinfunction "GPIO49_G2") (pintype "bidirectional"))
    )
    (net (code "73") (name "~{D17{slash}SCL1}") (class "Default")
      (node (ref "J3") (pin "11") (pinfunction "11_11") (pintype "passive"))
      (node (ref "U3") (pin "J3") (pinfunction "GPIO48_J3") (pintype "bidirectional"))
    )
    (net (code "74") (name "~{D18{slash}LED}") (class "Default")
      (node (ref "R12") (pin "2") (pinfunction "2_2") (pintype "passive"))
      (node (ref "U3") (pin "F3") (pinfunction "GPIO26_F3") (pintype "bidirectional"))
    )
    (net (code "75") (name "~{D19{slash}A0}") (class "Default")
      (node (ref "J2") (pin "6") (pinfunction "SWO_6") (pintype "bidirectional"))
      (node (ref "J4") (pin "5") (pinfunction "5_5") (pintype "passive"))
      (node (ref "U3") (pin "F8") (pinfunction "GPIO33_F8") (pintype "bidirectional"))
    )
    (net (code "76") (name "~{D20{slash}A1}") (class "Default")
      (node (ref "J4") (pin "6") (pinfunction "6_6") (pintype "passive"))
      (node (ref "U3") (pin "G8") (pinfunction "GPIO13_G8") (pintype "bidirectional"))
    )
    (net (code "77") (name "~{D21{slash}A2}") (class "Default")
      (node (ref "J4") (pin "7") (pinfunction "7_7") (pintype "passive"))
      (node (ref "U3") (pin "B9") (pinfunction "GPIO11_B9") (pintype "bidirectional"))
    )
    (net (code "78") (name "~{D22{slash}A3}") (class "Default")
      (node (ref "J4") (pin "8") (pinfunction "8_8") (pintype "passive"))
      (node (ref "U3") (pin "C9") (pinfunction "GPIO29_C9") (pintype "bidirectional"))
    )
    (net (code "79") (name "~{D23{slash}A4}") (class "Default")
      (node (ref "J4") (pin "9") (pinfunction "9_9") (pintype "passive"))
      (node (ref "U3") (pin "G9") (pinfunction "GPIO12_G9") (pintype "bidirectional"))
    )
    (net (code "80") (name "~{D24{slash}A5}") (class "Default")
      (node (ref "J4") (pin "10") (pinfunction "10_10") (pintype "passive"))
      (node (ref "U3") (pin "E7") (pinfunction "GPIO31_E7") (pintype "bidirectional"))
    )
    (net (code "81") (name "~{RESET}") (class "Default")
      (node (ref "C15") (pin "1") (pinfunction "1_1") (pintype "passive"))
      (node (ref "J2") (pin "10") (pinfunction "~{RESET}_10") (pintype "bidirectional"))
      (node (ref "J4") (pin "1") (pinfunction "1_1") (pintype "passive"))
      (node (ref "R11") (pin "1") (pinfunction "1_1") (pintype "passive"))
      (node (ref "S1") (pin "3") (pinfunction "2_3") (pintype "passive"))
      (node (ref "S1") (pin "4") (pinfunction "2_4") (pintype "passive"))
      (node (ref "U3") (pin "C1") (pinfunction "NRESET_C1") (pintype "bidirectional"))
    )
  )
)
